# SchemaAction.net
KiCad netlist of a schematic drawn in Altium Designer
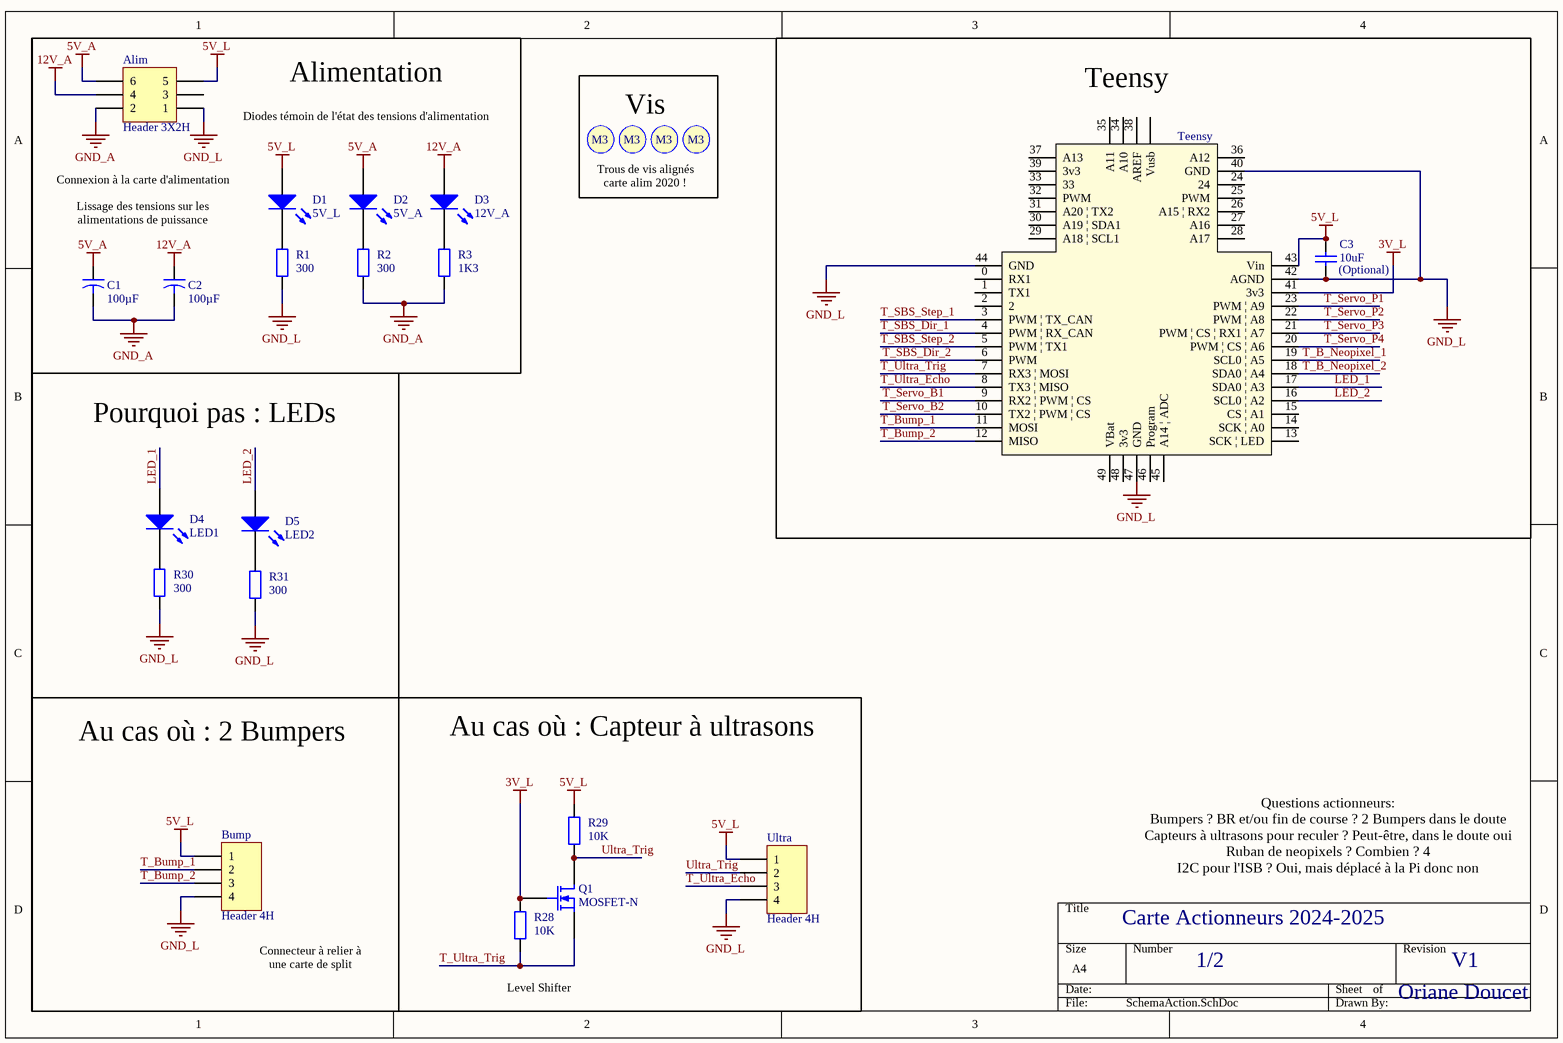
[diagram p0: SchemaAction.SchDoc]

(export (version "E")
  (design (tool "Eeschema 10.0.6"))
  (components
    (comp (ref "Alim")
      (value "Header 3X2H")
      (footprint "MOLEX_MINIFITJR_3X2")
      (description "Header, 3-Pin, Dual row, Right Angle")
      (fields (field (name "PUBLISHER") "Altium Limited"))
      (libsource (lib "Miscellaneous Connectors") (part "Header 3X2H"))
    )
    (comp (ref "Bump")
      (value "Header 4H")
      (footprint "S4B-XH-A")
      (description "Header, 4-Pin, Right Angle")
      (fields (field (name "PUBLISHER") "Altium Limited"))
      (libsource (lib "Miscellaneous Connectors") (part "Header 4H"))
    )
    (comp (ref "C1")
      (value "100µF")
      (footprint "Condensateur")
      (description "Capacitor")
      (fields (field (name "Comment") "Cap2") (field (name "PUBLISHER") "Altium Limited"))
      (libsource (lib "Miscellaneous Devices") (part "Cap2"))
    )
    (comp (ref "C2")
      (value "100µF")
      (footprint "Condensateur")
      (description "Capacitor")
      (fields (field (name "Comment") "Cap2") (field (name "PUBLISHER") "Altium Limited"))
      (libsource (lib "Miscellaneous Devices") (part "Cap2"))
    )
    (comp (ref "C3")
      (value "(Optional)")
      (footprint "Capacitor 1206")
      (description "Capacitor")
      (fields (field (name "ALTIUM_VALUE") "10uF") (field (name "PUBLISHER") "Altium Limited"))
      (libsource (lib "Miscellaneous Devices") (part "Cap"))
    )
    (comp (ref "D1")
      (value "5V_L")
      (footprint "KP-3216SEC")
      (description "Typical RED, GREEN, YELLOW, AMBER GaAs LED")
      (fields (field (name "PUBLISHER") "Altium Limited"))
      (libsource (lib "Miscellaneous Devices") (part "LED2"))
    )
    (comp (ref "D2")
      (value "5V_A")
      (footprint "KP-3216SEC")
      (description "Typical RED, GREEN, YELLOW, AMBER GaAs LED")
      (fields (field (name "PUBLISHER") "Altium Limited"))
      (libsource (lib "Miscellaneous Devices") (part "LED2"))
    )
    (comp (ref "D3")
      (value "12V_A")
      (footprint "KP-3216SEC")
      (description "Typical RED, GREEN, YELLOW, AMBER GaAs LED")
      (fields (field (name "PUBLISHER") "Altium Limited"))
      (libsource (lib "Miscellaneous Devices") (part "LED2"))
    )
    (comp (ref "D4")
      (value "LED1")
      (footprint "KP-3216SEC")
      (description "Typical RED, GREEN, YELLOW, AMBER GaAs LED")
      (fields (field (name "PUBLISHER") "Altium Limited"))
      (libsource (lib "Miscellaneous Devices") (part "LED2"))
    )
    (comp (ref "D5")
      (value "LED2")
      (footprint "KP-3216SEC")
      (description "Typical RED, GREEN, YELLOW, AMBER GaAs LED")
      (fields (field (name "PUBLISHER") "Altium Limited"))
      (libsource (lib "Miscellaneous Devices") (part "LED2"))
    )
    (comp (ref "Q1")
      (value "MOSFET-N")
      (footprint "SOT23_M")
      (description "N-Channel MOSFET")
      (fields (field (name "PUBLISHER") "Altium Limited"))
      (libsource (lib "Miscellaneous Devices") (part "MOSFET-N"))
    )
    (comp (ref "R1")
      (value "300")
      (footprint "Resistor 1206")
      (description "Resistor")
      (fields (field (name "Comment") "Res2") (field (name "PUBLISHER") "Altium Limited"))
      (libsource (lib "Miscellaneous Devices") (part "Res2"))
    )
    (comp (ref "R2")
      (value "300")
      (footprint "Resistor 1206")
      (description "Resistor")
      (fields (field (name "Comment") "Res2") (field (name "PUBLISHER") "Altium Limited"))
      (libsource (lib "") (part "Res2_1"))
    )
    (comp (ref "R3")
      (value "1K3")
      (footprint "Resistor 1206")
      (description "Resistor")
      (fields (field (name "Comment") "Res2") (field (name "PUBLISHER") "Altium Limited"))
      (libsource (lib "") (part "Res2_1"))
    )
    (comp (ref "R28")
      (value "10K")
      (footprint "Resistor 1206")
      (description "Resistor")
      (fields (field (name "Comment") "Res2") (field (name "PUBLISHER") "Altium Limited"))
      (libsource (lib "") (part "Res2_1"))
    )
    (comp (ref "R29")
      (value "10K")
      (footprint "Resistor 1206")
      (description "Resistor")
      (fields (field (name "Comment") "Res2") (field (name "PUBLISHER") "Altium Limited"))
      (libsource (lib "") (part "Res2_1"))
    )
    (comp (ref "R30")
      (value "300")
      (footprint "Resistor 1206")
      (description "Resistor")
      (fields (field (name "Comment") "Res2") (field (name "PUBLISHER") "Altium Limited"))
      (libsource (lib "Miscellaneous Devices") (part "Res2"))
    )
    (comp (ref "R31")
      (value "300")
      (footprint "Resistor 1206")
      (description "Resistor")
      (fields (field (name "Comment") "Res2") (field (name "PUBLISHER") "Altium Limited"))
      (libsource (lib "Miscellaneous Devices") (part "Res2"))
    )
    (comp (ref "S1")
      (value "Screw M3")
      (footprint "Screw M3")
      (libsource (lib "Robot_2019") (part "Screw M3"))
    )
    (comp (ref "S2")
      (value "Screw M3")
      (footprint "Screw M3")
      (libsource (lib "Robot_2019") (part "Screw M3"))
    )
    (comp (ref "S3")
      (value "Screw M3")
      (footprint "Screw M3")
      (libsource (lib "Robot_2019") (part "Screw M3"))
    )
    (comp (ref "S4")
      (value "Screw M3")
      (footprint "Screw M3")
      (libsource (lib "Robot_2019") (part "Screw M3"))
    )
    (comp (ref "Teensy")
      (value "Teensy 3.2")
      (footprint "teensy")
      (libsource (lib "Robot_2020") (part "teensy3.2"))
    )
    (comp (ref "Ultra")
      (value "Header 4H")
      (footprint "S4B-XH-A")
      (description "Header, 4-Pin, Right Angle")
      (fields (field (name "PUBLISHER") "Altium Limited"))
      (libsource (lib "Miscellaneous Connectors") (part "Header 4H"))
    )
  )
  (nets
    (net (code "1") (name "/LED_1") (class "Default")
      (node (ref "D4") (pin "1") (pinfunction "A_1") (pintype "passive"))
      (node (ref "Teensy") (pin "17") (pinfunction "SDA0_¦_A3_17") (pintype "passive"))
    )
    (net (code "2") (name "/LED_2") (class "Default")
      (node (ref "D5") (pin "1") (pinfunction "A_1") (pintype "passive"))
      (node (ref "Teensy") (pin "16") (pinfunction "SCL0_¦_A2_16") (pintype "passive"))
    )
    (net (code "3") (name "/T_B_Neopixel_1") (class "Default")
      (node (ref "Teensy") (pin "19") (pinfunction "SCL0_¦_A5_19") (pintype "passive"))
    )
    (net (code "4") (name "/T_B_Neopixel_2") (class "Default")
      (node (ref "Teensy") (pin "18") (pinfunction "SDA0_¦_A4_18") (pintype "passive"))
    )
    (net (code "5") (name "/T_Bump_1") (class "Default")
      (node (ref "Bump") (pin "2") (pinfunction "2_2") (pintype "passive"))
      (node (ref "Teensy") (pin "11") (pinfunction "MOSI_11") (pintype "passive"))
    )
    (net (code "6") (name "/T_Bump_2") (class "Default")
      (node (ref "Bump") (pin "3") (pinfunction "3_3") (pintype "passive"))
      (node (ref "Teensy") (pin "12") (pinfunction "MISO_12") (pintype "passive"))
    )
    (net (code "7") (name "/T_SBS_Dir_1") (class "Default")
      (node (ref "Teensy") (pin "4") (pinfunction "PWM_¦_RX_CAN_4") (pintype "passive"))
    )
    (net (code "8") (name "/T_SBS_Dir_2") (class "Default")
      (node (ref "Teensy") (pin "6") (pinfunction "PWM_6") (pintype "passive"))
    )
    (net (code "9") (name "/T_SBS_Step_1") (class "Default")
      (node (ref "Teensy") (pin "3") (pinfunction "PWM_¦_TX_CAN_3") (pintype "passive"))
    )
    (net (code "10") (name "/T_SBS_Step_2") (class "Default")
      (node (ref "Teensy") (pin "5") (pinfunction "PWM_¦_TX1_5") (pintype "passive"))
    )
    (net (code "11") (name "/T_Servo_B1") (class "Default")
      (node (ref "Teensy") (pin "9") (pinfunction "RX2_¦_PWM_¦_CS_9") (pintype "passive"))
    )
    (net (code "12") (name "/T_Servo_B2") (class "Default")
      (node (ref "Teensy") (pin "10") (pinfunction "TX2_¦_PWM_¦_CS_10") (pintype "passive"))
    )
    (net (code "13") (name "/T_Servo_P1") (class "Default")
      (node (ref "Teensy") (pin "23") (pinfunction "PWM_¦_A9_23") (pintype "passive"))
    )
    (net (code "14") (name "/T_Servo_P2") (class "Default")
      (node (ref "Teensy") (pin "22") (pinfunction "PWM_¦_A8_22") (pintype "passive"))
    )
    (net (code "15") (name "/T_Servo_P3") (class "Default")
      (node (ref "Teensy") (pin "21") (pinfunction "PWM_¦_CS_¦_RX1_¦_A7_21") (pintype "passive"))
    )
    (net (code "16") (name "/T_Servo_P4") (class "Default")
      (node (ref "Teensy") (pin "20") (pinfunction "PWM_¦_CS_¦_A6_20") (pintype "passive"))
    )
    (net (code "17") (name "/T_Ultra_Echo") (class "Default")
      (node (ref "Teensy") (pin "8") (pinfunction "TX3_¦_MISO_8") (pintype "passive"))
      (node (ref "Ultra") (pin "3") (pinfunction "3_3") (pintype "passive"))
    )
    (net (code "18") (name "/T_Ultra_Trig") (class "Default")
      (node (ref "Q1") (pin "3") (pinfunction "S_3") (pintype "passive"))
      (node (ref "R28") (pin "2") (pinfunction "2_2") (pintype "passive"))
      (node (ref "Teensy") (pin "7") (pinfunction "RX3_¦_MOSI_7") (pintype "passive"))
    )
    (net (code "19") (name "/Ultra_Trig") (class "Default")
      (node (ref "Q1") (pin "1") (pinfunction "D_1") (pintype "passive"))
      (node (ref "R29") (pin "2") (pinfunction "2_2") (pintype "passive"))
      (node (ref "Ultra") (pin "2") (pinfunction "2_2") (pintype "passive"))
    )
    (net (code "20") (name "3V_L") (class "Default")
      (node (ref "Q1") (pin "2") (pinfunction "G_2") (pintype "passive"))
      (node (ref "R28") (pin "1") (pinfunction "1_1") (pintype "passive"))
      (node (ref "Teensy") (pin "41") (pinfunction "3v3_41") (pintype "passive"))
    )
    (net (code "21") (name "5V_A") (class "Default")
      (node (ref "Alim") (pin "6") (pinfunction "6_6") (pintype "passive"))
      (node (ref "C1") (pin "1") (pinfunction "1_1") (pintype "passive"))
      (node (ref "D2") (pin "1") (pinfunction "A_1") (pintype "passive"))
    )
    (net (code "22") (name "5V_L") (class "Default")
      (node (ref "Alim") (pin "5") (pinfunction "5_5") (pintype "passive"))
      (node (ref "Bump") (pin "1") (pinfunction "1_1") (pintype "passive"))
      (node (ref "C3") (pin "2") (pinfunction "2_2") (pintype "passive"))
      (node (ref "D1") (pin "1") (pinfunction "A_1") (pintype "passive"))
      (node (ref "R29") (pin "1") (pinfunction "1_1") (pintype "passive"))
      (node (ref "Teensy") (pin "43") (pinfunction "Vin_43") (pintype "passive"))
      (node (ref "Ultra") (pin "1") (pinfunction "1_1") (pintype "passive"))
    )
    (net (code "23") (name "12V_A") (class "Default")
      (node (ref "Alim") (pin "4") (pinfunction "4_4") (pintype "passive"))
      (node (ref "C2") (pin "1") (pinfunction "1_1") (pintype "passive"))
      (node (ref "D3") (pin "1") (pinfunction "A_1") (pintype "passive"))
    )
    (net (code "24") (name "GND_A") (class "Default")
      (node (ref "Alim") (pin "2") (pinfunction "2_2") (pintype "passive"))
      (node (ref "C1") (pin "2") (pinfunction "2_2") (pintype "passive"))
      (node (ref "C2") (pin "2") (pinfunction "2_2") (pintype "passive"))
      (node (ref "R2") (pin "2") (pinfunction "2_2") (pintype "passive"))
      (node (ref "R3") (pin "2") (pinfunction "2_2") (pintype "passive"))
    )
    (net (code "25") (name "GND_L") (class "Default")
      (node (ref "Alim") (pin "1") (pinfunction "1_1") (pintype "passive"))
      (node (ref "Bump") (pin "4") (pinfunction "4_4") (pintype "passive"))
      (node (ref "C3") (pin "1") (pinfunction "1_1") (pintype "passive"))
      (node (ref "R1") (pin "1") (pinfunction "1_1") (pintype "passive"))
      (node (ref "R30") (pin "1") (pinfunction "1_1") (pintype "passive"))
      (node (ref "R31") (pin "1") (pinfunction "1_1") (pintype "passive"))
      (node (ref "Teensy") (pin "40") (pinfunction "GND_40") (pintype "passive"))
      (node (ref "Teensy") (pin "42") (pinfunction "AGND_42") (pintype "passive"))
      (node (ref "Teensy") (pin "44") (pinfunction "GND_44") (pintype "passive"))
      (node (ref "Teensy") (pin "47") (pinfunction "GND_47") (pintype "passive"))
      (node (ref "Ultra") (pin "4") (pinfunction "4_4") (pintype "passive"))
    )
    (net (code "26") (name "Net-(D1-K)") (class "Default")
      (node (ref "D1") (pin "2") (pinfunction "K_2") (pintype "passive"))
      (node (ref "R1") (pin "2") (pinfunction "2_2") (pintype "passive"))
    )
    (net (code "27") (name "Net-(D2-K)") (class "Default")
      (node (ref "D2") (pin "2") (pinfunction "K_2") (pintype "passive"))
      (node (ref "R2") (pin "1") (pinfunction "1_1") (pintype "passive"))
    )
    (net (code "28") (name "Net-(D3-K)") (class "Default")
      (node (ref "D3") (pin "2") (pinfunction "K_2") (pintype "passive"))
      (node (ref "R3") (pin "1") (pinfunction "1_1") (pintype "passive"))
    )
    (net (code "29") (name "Net-(D4-K)") (class "Default")
      (node (ref "D4") (pin "2") (pinfunction "K_2") (pintype "passive"))
      (node (ref "R30") (pin "2") (pinfunction "2_2") (pintype "passive"))
    )
    (net (code "30") (name "Net-(D5-K)") (class "Default")
      (node (ref "D5") (pin "2") (pinfunction "K_2") (pintype "passive"))
      (node (ref "R31") (pin "2") (pinfunction "2_2") (pintype "passive"))
    )
    (net (code "31") (name "unconnected-(Alim-Pad3)") (class "Default")
      (node (ref "Alim") (pin "3") (pinfunction "3_3") (pintype "passive"))
    )
    (net (code "32") (name "unconnected-(Teensy-3v3-Pad39)") (class "Default")
      (node (ref "Teensy") (pin "39") (pinfunction "3v3_39") (pintype "passive"))
    )
    (net (code "33") (name "unconnected-(Teensy-3v3-Pad48)") (class "Default")
      (node (ref "Teensy") (pin "48") (pinfunction "3v3_48") (pintype "passive"))
    )
    (net (code "34") (name "unconnected-(Teensy-A10-Pad34)") (class "Default")
      (node (ref "Teensy") (pin "34") (pinfunction "A10_34") (pintype "passive"))
    )
    (net (code "35") (name "unconnected-(Teensy-A11-Pad35)") (class "Default")
      (node (ref "Teensy") (pin "35") (pinfunction "A11_35") (pintype "passive"))
    )
    (net (code "36") (name "unconnected-(Teensy-A12-Pad36)") (class "Default")
      (node (ref "Teensy") (pin "36") (pinfunction "A12_36") (pintype "passive"))
    )
    (net (code "37") (name "unconnected-(Teensy-A13-Pad37)") (class "Default")
      (node (ref "Teensy") (pin "37") (pinfunction "A13_37") (pintype "passive"))
    )
    (net (code "38") (name "unconnected-(Teensy-A14_¦_ADC-Pad45)") (class "Default")
      (node (ref "Teensy") (pin "45") (pinfunction "A14_¦_ADC_45") (pintype "passive"))
    )
    (net (code "39") (name "unconnected-(Teensy-A15_¦_RX2-Pad26)") (class "Default")
      (node (ref "Teensy") (pin "26") (pinfunction "A15_¦_RX2_26") (pintype "passive"))
    )
    (net (code "40") (name "unconnected-(Teensy-A16-Pad27)") (class "Default")
      (node (ref "Teensy") (pin "27") (pinfunction "A16_27") (pintype "passive"))
    )
    (net (code "41") (name "unconnected-(Teensy-A17-Pad28)") (class "Default")
      (node (ref "Teensy") (pin "28") (pinfunction "A17_28") (pintype "passive"))
    )
    (net (code "42") (name "unconnected-(Teensy-A18_¦_SCL1-Pad29)") (class "Default")
      (node (ref "Teensy") (pin "29") (pinfunction "A18_¦_SCL1_29") (pintype "passive"))
    )
    (net (code "43") (name "unconnected-(Teensy-A19_¦_SDA1-Pad30)") (class "Default")
      (node (ref "Teensy") (pin "30") (pinfunction "A19_¦_SDA1_30") (pintype "passive"))
    )
    (net (code "44") (name "unconnected-(Teensy-A20_¦_TX2-Pad31)") (class "Default")
      (node (ref "Teensy") (pin "31") (pinfunction "A20_¦_TX2_31") (pintype "passive"))
    )
    (net (code "45") (name "unconnected-(Teensy-AREF-Pad38)") (class "Default")
      (node (ref "Teensy") (pin "38") (pinfunction "AREF_38") (pintype "passive"))
    )
    (net (code "46") (name "unconnected-(Teensy-CS_¦_A1-Pad15)") (class "Default")
      (node (ref "Teensy") (pin "15") (pinfunction "CS_¦_A1_15") (pintype "passive"))
    )
    (net (code "47") (name "unconnected-(Teensy-PWM-Pad25)") (class "Default")
      (node (ref "Teensy") (pin "25") (pinfunction "PWM_25") (pintype "passive"))
    )
    (net (code "48") (name "unconnected-(Teensy-PWM-Pad32)") (class "Default")
      (node (ref "Teensy") (pin "32") (pinfunction "PWM_32") (pintype "passive"))
    )
    (net (code "49") (name "unconnected-(Teensy-Pad2)") (class "Default")
      (node (ref "Teensy") (pin "2") (pinfunction "2_2") (pintype "passive"))
    )
    (net (code "50") (name "unconnected-(Teensy-Pad24)") (class "Default")
      (node (ref "Teensy") (pin "24") (pinfunction "24_24") (pintype "passive"))
    )
    (net (code "51") (name "unconnected-(Teensy-Pad33)") (class "Default")
      (node (ref "Teensy") (pin "33") (pinfunction "33_33") (pintype "passive"))
    )
    (net (code "52") (name "unconnected-(Teensy-Program-Pad46)") (class "Default")
      (node (ref "Teensy") (pin "46") (pinfunction "Program_46") (pintype "passive"))
    )
    (net (code "53") (name "unconnected-(Teensy-RX1-Pad0)") (class "Default")
      (node (ref "Teensy") (pin "0") (pinfunction "RX1_0") (pintype "passive"))
    )
    (net (code "54") (name "unconnected-(Teensy-SCK_¦_A0-Pad14)") (class "Default")
      (node (ref "Teensy") (pin "14") (pinfunction "SCK_¦_A0_14") (pintype "passive"))
    )
    (net (code "55") (name "unconnected-(Teensy-SCK_¦_LED-Pad13)") (class "Default")
      (node (ref "Teensy") (pin "13") (pinfunction "SCK_¦_LED_13") (pintype "passive"))
    )
    (net (code "56") (name "unconnected-(Teensy-TX1-Pad1)") (class "Default")
      (node (ref "Teensy") (pin "1") (pinfunction "TX1_1") (pintype "passive"))
    )
    (net (code "57") (name "unconnected-(Teensy-VBat-Pad49)") (class "Default")
      (node (ref "Teensy") (pin "49") (pinfunction "VBat_49") (pintype "passive"))
    )
    (net (code "58") (name "unconnected-(Teensy-Vusb-Pad50)") (class "Default")
      (node (ref "Teensy") (pin "50") (pinfunction "Vusb_50") (pintype "passive"))
    )
  )
)
